# 0113-phobos.net
KiCad netlist of a schematic drawn in EAGLE
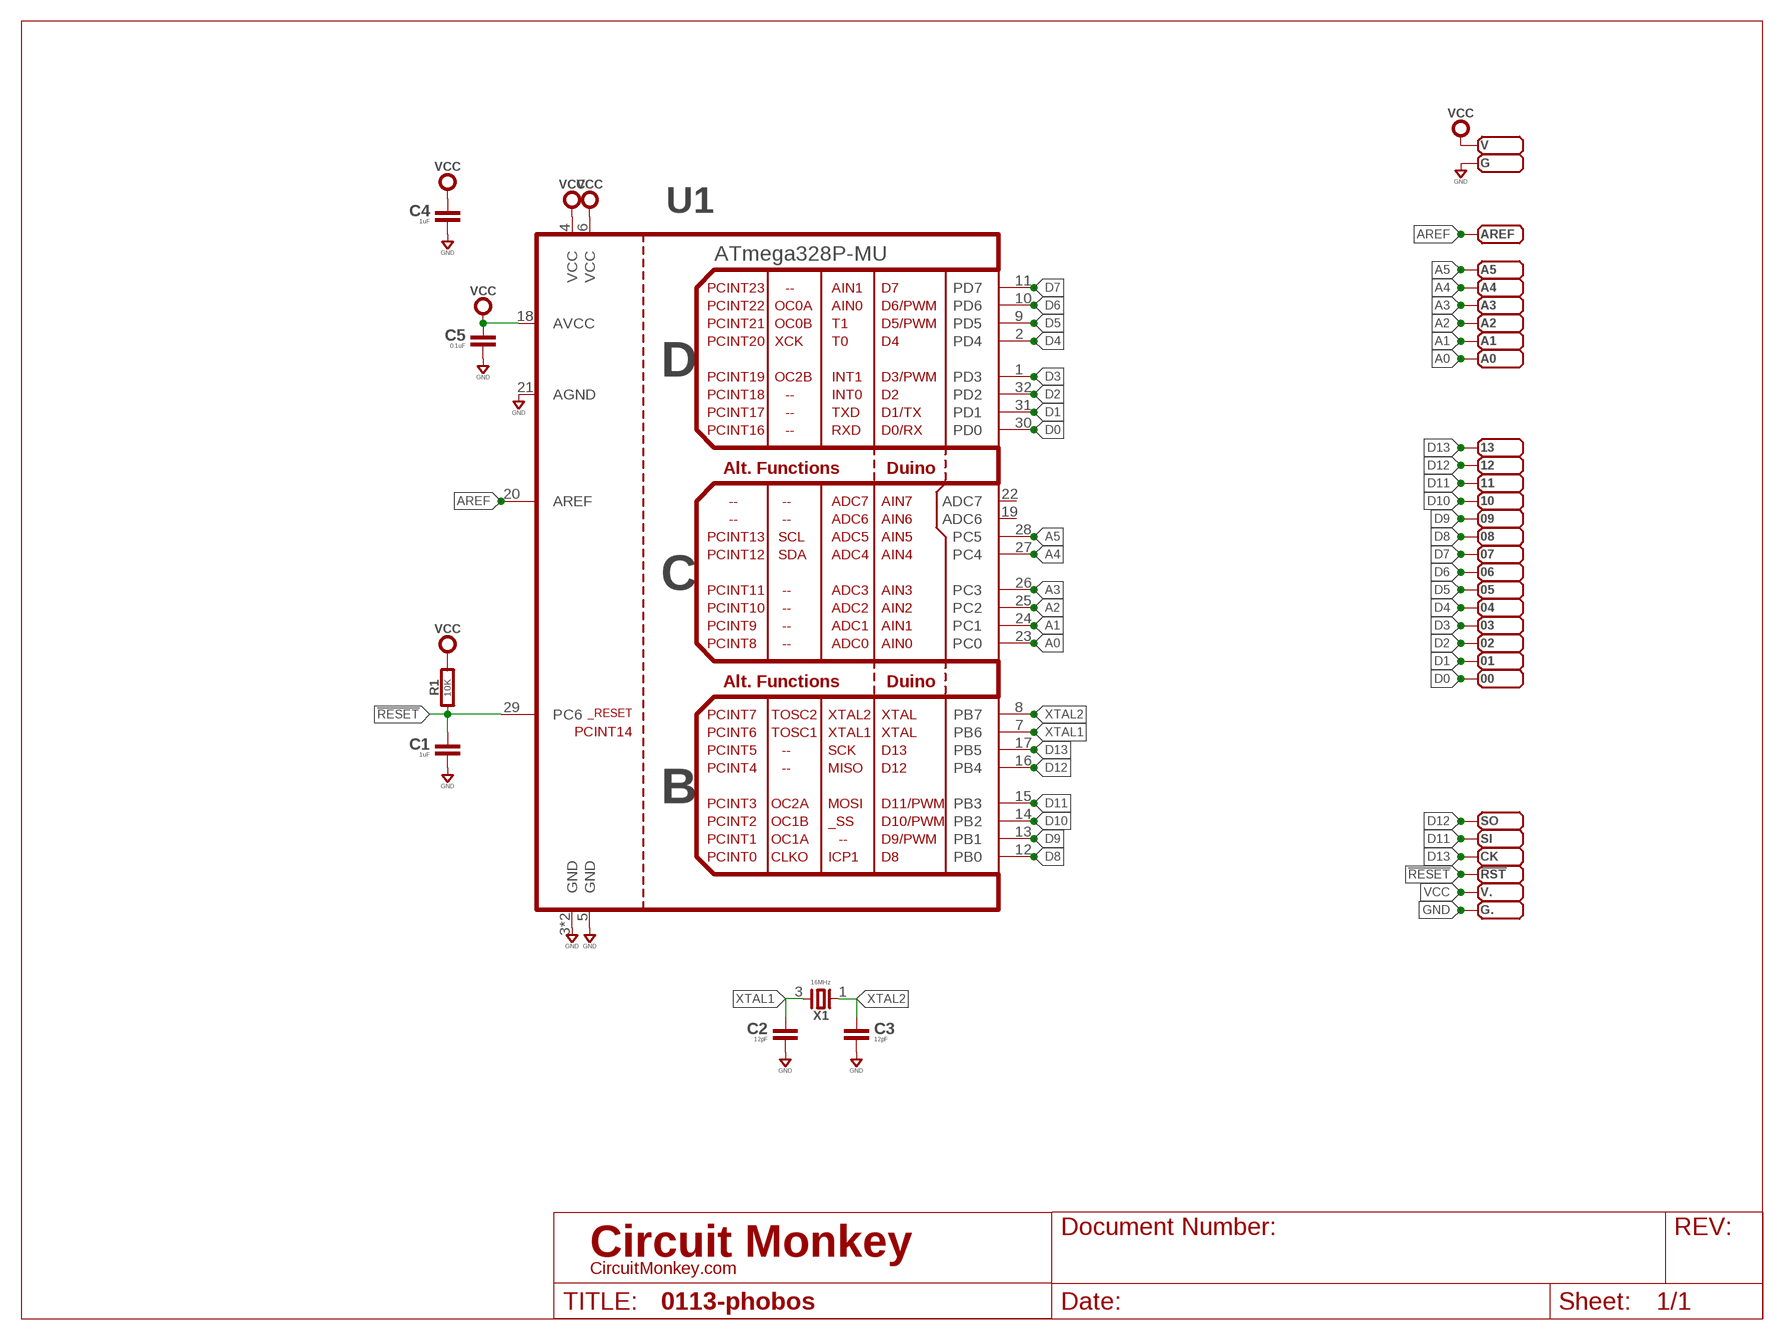
[diagram p0: schematic, sheet 1]

(export (version "E")
  (design (tool "Eeschema 10.0.6"))
  (components
    (comp (ref "!RST")
      (value "PADSMD-070X070")
      (footprint "eagle-import:SMD-070MIL")
      (libsource (lib "eagle-import") (part "PADSMD-070X070"))
    )
    (comp (ref "00")
      (value "PADSMD-070X070")
      (footprint "eagle-import:SMD-070MIL")
      (libsource (lib "eagle-import") (part "PADSMD-070X070"))
    )
    (comp (ref "01")
      (value "PADSMD-070X070")
      (footprint "eagle-import:SMD-070MIL")
      (libsource (lib "eagle-import") (part "PADSMD-070X070"))
    )
    (comp (ref "02")
      (value "PADSMD-070X070")
      (footprint "eagle-import:SMD-070MIL")
      (libsource (lib "eagle-import") (part "PADSMD-070X070"))
    )
    (comp (ref "03")
      (value "PADSMD-070X070")
      (footprint "eagle-import:SMD-070MIL")
      (libsource (lib "eagle-import") (part "PADSMD-070X070"))
    )
    (comp (ref "04")
      (value "PADSMD-070X070")
      (footprint "eagle-import:SMD-070MIL")
      (libsource (lib "eagle-import") (part "PADSMD-070X070"))
    )
    (comp (ref "05")
      (value "PADSMD-070X070")
      (footprint "eagle-import:SMD-070MIL")
      (libsource (lib "eagle-import") (part "PADSMD-070X070"))
    )
    (comp (ref "06")
      (value "PADSMD-070X070")
      (footprint "eagle-import:SMD-070MIL")
      (libsource (lib "eagle-import") (part "PADSMD-070X070"))
    )
    (comp (ref "07")
      (value "PADSMD-070X070")
      (footprint "eagle-import:SMD-070MIL")
      (libsource (lib "eagle-import") (part "PADSMD-070X070"))
    )
    (comp (ref "08")
      (value "PADSMD-070X070")
      (footprint "eagle-import:SMD-070MIL")
      (libsource (lib "eagle-import") (part "PADSMD-070X070"))
    )
    (comp (ref "09")
      (value "PADSMD-070X070")
      (footprint "eagle-import:SMD-070MIL")
      (libsource (lib "eagle-import") (part "PADSMD-070X070"))
    )
    (comp (ref "10")
      (value "PADSMD-070X070")
      (footprint "eagle-import:SMD-070MIL")
      (libsource (lib "eagle-import") (part "PADSMD-070X070"))
    )
    (comp (ref "11")
      (value "PADSMD-070X070")
      (footprint "eagle-import:SMD-070MIL")
      (libsource (lib "eagle-import") (part "PADSMD-070X070"))
    )
    (comp (ref "12")
      (value "PADSMD-070X070")
      (footprint "eagle-import:SMD-070MIL")
      (libsource (lib "eagle-import") (part "PADSMD-070X070"))
    )
    (comp (ref "13")
      (value "PADSMD-070X070")
      (footprint "eagle-import:SMD-070MIL")
      (libsource (lib "eagle-import") (part "PADSMD-070X070"))
    )
    (comp (ref "A0")
      (value "PADSMD-070X070")
      (footprint "eagle-import:SMD-070MIL")
      (libsource (lib "eagle-import") (part "PADSMD-070X070"))
    )
    (comp (ref "A1")
      (value "PADSMD-070X070")
      (footprint "eagle-import:SMD-070MIL")
      (libsource (lib "eagle-import") (part "PADSMD-070X070"))
    )
    (comp (ref "A2")
      (value "PADSMD-070X070")
      (footprint "eagle-import:SMD-070MIL")
      (libsource (lib "eagle-import") (part "PADSMD-070X070"))
    )
    (comp (ref "A3")
      (value "PADSMD-070X070")
      (footprint "eagle-import:SMD-070MIL")
      (libsource (lib "eagle-import") (part "PADSMD-070X070"))
    )
    (comp (ref "A4")
      (value "PADSMD-070X070")
      (footprint "eagle-import:SMD-070MIL")
      (libsource (lib "eagle-import") (part "PADSMD-070X070"))
    )
    (comp (ref "A5")
      (value "PADSMD-070X070")
      (footprint "eagle-import:SMD-070MIL")
      (libsource (lib "eagle-import") (part "PADSMD-070X070"))
    )
    (comp (ref "AREF")
      (value "PADSMD-070X070")
      (footprint "eagle-import:SMD-070MIL")
      (libsource (lib "eagle-import") (part "PADSMD-070X070"))
    )
    (comp (ref "C1")
      (value "1uF")
      (footprint "eagle-import:0402-CAP")
      (libsource (lib "eagle-import") (part "CAPACITOR0402"))
    )
    (comp (ref "C2")
      (value "12pF")
      (footprint "eagle-import:0402-CAP")
      (libsource (lib "eagle-import") (part "CAPACITOR0402"))
    )
    (comp (ref "C3")
      (value "12pF")
      (footprint "eagle-import:0402-CAP")
      (libsource (lib "eagle-import") (part "CAPACITOR0402"))
    )
    (comp (ref "C4")
      (value "1uF")
      (footprint "eagle-import:0402-CAP")
      (libsource (lib "eagle-import") (part "CAPACITOR0402"))
    )
    (comp (ref "C5")
      (value "0.1uF")
      (footprint "eagle-import:0402-CAP")
      (libsource (lib "eagle-import") (part "CAPACITOR0402"))
    )
    (comp (ref "CK")
      (value "PADSMD-070X070")
      (footprint "eagle-import:SMD-070MIL")
      (libsource (lib "eagle-import") (part "PADSMD-070X070"))
    )
    (comp (ref "G")
      (value "PADSMD-070X070")
      (footprint "eagle-import:SMD-070MIL")
      (libsource (lib "eagle-import") (part "PADSMD-070X070"))
    )
    (comp (ref "G.")
      (value "PADSMD-070X070")
      (footprint "eagle-import:SMD-070MIL")
      (libsource (lib "eagle-import") (part "PADSMD-070X070"))
    )
    (comp (ref "R1")
      (value "10K")
      (footprint "eagle-import:0402-RES")
      (libsource (lib "eagle-import") (part "RESISTOR0402"))
    )
    (comp (ref "SI")
      (value "PADSMD-070X070")
      (footprint "eagle-import:SMD-070MIL")
      (libsource (lib "eagle-import") (part "PADSMD-070X070"))
    )
    (comp (ref "SO")
      (value "PADSMD-070X070")
      (footprint "eagle-import:SMD-070MIL")
      (libsource (lib "eagle-import") (part "PADSMD-070X070"))
    )
    (comp (ref "U1")
      (value "ATmega328P-MU")
      (footprint "eagle-import:MLF32")
      (fields (field (name "MF") "Atmel") (field (name "MPN") "atmega328p-mu"))
      (libsource (lib "eagle-import") (part "ATMEGA328MU"))
    )
    (comp (ref "V")
      (value "PADSMD-070X070")
      (footprint "eagle-import:SMD-070MIL")
      (libsource (lib "eagle-import") (part "PADSMD-070X070"))
    )
    (comp (ref "V.")
      (value "PADSMD-070X070")
      (footprint "eagle-import:SMD-070MIL")
      (libsource (lib "eagle-import") (part "PADSMD-070X070"))
    )
    (comp (ref "X1")
      (value "16MHz")
      (footprint "eagle-import:32X25")
      (fields (field (name "MF") "Epson") (field (name "MPN") "FA-238 16.0000MB-K3"))
      (libsource (lib "eagle-import") (part "2P3.2X2.5"))
    )
  )
  (nets
    (net (code "1") (name "/~{RESET}") (class "Default")
      (node (ref "!RST") (pin "1") (pinfunction "PAD_1") (pintype "bidirectional"))
      (node (ref "C1") (pin "1") (pinfunction "1_1") (pintype "passive"))
      (node (ref "R1") (pin "1") (pinfunction "1_1") (pintype "passive"))
      (node (ref "U1") (pin "29") (pinfunction "PC6_29") (pintype "bidirectional"))
    )
    (net (code "2") (name "A0") (class "Default")
      (node (ref "A0") (pin "1") (pinfunction "PAD_1") (pintype "bidirectional"))
      (node (ref "U1") (pin "23") (pinfunction "PC0_23") (pintype "bidirectional"))
    )
    (net (code "3") (name "A1") (class "Default")
      (node (ref "A1") (pin "1") (pinfunction "PAD_1") (pintype "bidirectional"))
      (node (ref "U1") (pin "24") (pinfunction "PC1_24") (pintype "bidirectional"))
    )
    (net (code "4") (name "A2") (class "Default")
      (node (ref "A2") (pin "1") (pinfunction "PAD_1") (pintype "bidirectional"))
      (node (ref "U1") (pin "25") (pinfunction "PC2_25") (pintype "bidirectional"))
    )
    (net (code "5") (name "A3") (class "Default")
      (node (ref "A3") (pin "1") (pinfunction "PAD_1") (pintype "bidirectional"))
      (node (ref "U1") (pin "26") (pinfunction "PC3_26") (pintype "bidirectional"))
    )
    (net (code "6") (name "A4") (class "Default")
      (node (ref "A4") (pin "1") (pinfunction "PAD_1") (pintype "bidirectional"))
      (node (ref "U1") (pin "27") (pinfunction "PC4_27") (pintype "bidirectional"))
    )
    (net (code "7") (name "A5") (class "Default")
      (node (ref "A5") (pin "1") (pinfunction "PAD_1") (pintype "bidirectional"))
      (node (ref "U1") (pin "28") (pinfunction "PC5_28") (pintype "bidirectional"))
    )
    (net (code "8") (name "AREF") (class "Default")
      (node (ref "AREF") (pin "1") (pinfunction "PAD_1") (pintype "bidirectional"))
      (node (ref "U1") (pin "20") (pinfunction "AREF_20") (pintype "input"))
    )
    (net (code "9") (name "D0") (class "Default")
      (node (ref "00") (pin "1") (pinfunction "PAD_1") (pintype "bidirectional"))
      (node (ref "U1") (pin "30") (pinfunction "PD0_30") (pintype "bidirectional"))
    )
    (net (code "10") (name "D1") (class "Default")
      (node (ref "01") (pin "1") (pinfunction "PAD_1") (pintype "bidirectional"))
      (node (ref "U1") (pin "31") (pinfunction "PD1_31") (pintype "bidirectional"))
    )
    (net (code "11") (name "D2") (class "Default")
      (node (ref "02") (pin "1") (pinfunction "PAD_1") (pintype "bidirectional"))
      (node (ref "U1") (pin "32") (pinfunction "PD2_32") (pintype "bidirectional"))
    )
    (net (code "12") (name "D3") (class "Default")
      (node (ref "03") (pin "1") (pinfunction "PAD_1") (pintype "bidirectional"))
      (node (ref "U1") (pin "1") (pinfunction "PD3_1") (pintype "bidirectional"))
    )
    (net (code "13") (name "D4") (class "Default")
      (node (ref "04") (pin "1") (pinfunction "PAD_1") (pintype "bidirectional"))
      (node (ref "U1") (pin "2") (pinfunction "PD4_2") (pintype "bidirectional"))
    )
    (net (code "14") (name "D5") (class "Default")
      (node (ref "05") (pin "1") (pinfunction "PAD_1") (pintype "bidirectional"))
      (node (ref "U1") (pin "9") (pinfunction "PD5_9") (pintype "bidirectional"))
    )
    (net (code "15") (name "D6") (class "Default")
      (node (ref "06") (pin "1") (pinfunction "PAD_1") (pintype "bidirectional"))
      (node (ref "U1") (pin "10") (pinfunction "PD6_10") (pintype "bidirectional"))
    )
    (net (code "16") (name "D7") (class "Default")
      (node (ref "07") (pin "1") (pinfunction "PAD_1") (pintype "bidirectional"))
      (node (ref "U1") (pin "11") (pinfunction "PD7_11") (pintype "bidirectional"))
    )
    (net (code "17") (name "D8") (class "Default")
      (node (ref "08") (pin "1") (pinfunction "PAD_1") (pintype "bidirectional"))
      (node (ref "U1") (pin "12") (pinfunction "PB0_12") (pintype "bidirectional"))
    )
    (net (code "18") (name "D9") (class "Default")
      (node (ref "09") (pin "1") (pinfunction "PAD_1") (pintype "bidirectional"))
      (node (ref "U1") (pin "13") (pinfunction "PB1_13") (pintype "bidirectional"))
    )
    (net (code "19") (name "D10") (class "Default")
      (node (ref "10") (pin "1") (pinfunction "PAD_1") (pintype "bidirectional"))
      (node (ref "U1") (pin "14") (pinfunction "PB2_14") (pintype "bidirectional"))
    )
    (net (code "20") (name "D11") (class "Default")
      (node (ref "11") (pin "1") (pinfunction "PAD_1") (pintype "bidirectional"))
      (node (ref "SI") (pin "1") (pinfunction "PAD_1") (pintype "bidirectional"))
      (node (ref "U1") (pin "15") (pinfunction "PB3_15") (pintype "bidirectional"))
    )
    (net (code "21") (name "D12") (class "Default")
      (node (ref "12") (pin "1") (pinfunction "PAD_1") (pintype "bidirectional"))
      (node (ref "SO") (pin "1") (pinfunction "PAD_1") (pintype "bidirectional"))
      (node (ref "U1") (pin "16") (pinfunction "PB4_16") (pintype "bidirectional"))
    )
    (net (code "22") (name "D13") (class "Default")
      (node (ref "13") (pin "1") (pinfunction "PAD_1") (pintype "bidirectional"))
      (node (ref "CK") (pin "1") (pinfunction "PAD_1") (pintype "bidirectional"))
      (node (ref "U1") (pin "17") (pinfunction "PB5_17") (pintype "bidirectional"))
    )
    (net (code "23") (name "GND") (class "Default")
      (node (ref "C1") (pin "2") (pinfunction "2_2") (pintype "passive"))
      (node (ref "C2") (pin "2") (pinfunction "2_2") (pintype "passive"))
      (node (ref "C3") (pin "2") (pinfunction "2_2") (pintype "passive"))
      (node (ref "C4") (pin "2") (pinfunction "2_2") (pintype "passive"))
      (node (ref "C5") (pin "2") (pinfunction "2_2") (pintype "passive"))
      (node (ref "G") (pin "1") (pinfunction "PAD_1") (pintype "bidirectional"))
      (node (ref "G.") (pin "1") (pinfunction "PAD_1") (pintype "bidirectional"))
      (node (ref "U1") (pin "21") (pinfunction "AGND_21") (pintype "power_in"))
      (node (ref "U1") (pin "3") (pinfunction "GND_3") (pintype "power_in"))
      (node (ref "U1") (pin "5") (pinfunction "GND_5") (pintype "power_in"))
      (node (ref "U1") (pin "PAD") (pinfunction "GND_PAD") (pintype "power_in"))
    )
    (net (code "24") (name "VCC") (class "Default")
      (node (ref "C4") (pin "1") (pinfunction "1_1") (pintype "passive"))
      (node (ref "C5") (pin "1") (pinfunction "1_1") (pintype "passive"))
      (node (ref "R1") (pin "2") (pinfunction "2_2") (pintype "passive"))
      (node (ref "U1") (pin "18") (pinfunction "AVCC_18") (pintype "power_in"))
      (node (ref "U1") (pin "4") (pinfunction "VCC_4") (pintype "power_in"))
      (node (ref "U1") (pin "6") (pinfunction "VCC_6") (pintype "power_in"))
      (node (ref "V") (pin "1") (pinfunction "PAD_1") (pintype "bidirectional"))
      (node (ref "V.") (pin "1") (pinfunction "PAD_1") (pintype "bidirectional"))
    )
    (net (code "25") (name "XTAL1") (class "Default")
      (node (ref "C2") (pin "1") (pinfunction "1_1") (pintype "passive"))
      (node (ref "U1") (pin "7") (pinfunction "PB6_7") (pintype "bidirectional"))
      (node (ref "X1") (pin "3") (pinfunction "P$2_3") (pintype "passive"))
    )
    (net (code "26") (name "XTAL2") (class "Default")
      (node (ref "C3") (pin "1") (pinfunction "1_1") (pintype "passive"))
      (node (ref "U1") (pin "8") (pinfunction "PB7_8") (pintype "bidirectional"))
      (node (ref "X1") (pin "1") (pinfunction "P$1_1") (pintype "passive"))
    )
    (net (code "27") (name "unconnected-(U1-ADC6-Pad19)") (class "Default")
      (node (ref "U1") (pin "19") (pinfunction "ADC6_19") (pintype "bidirectional"))
    )
    (net (code "28") (name "unconnected-(U1-ADC7-Pad22)") (class "Default")
      (node (ref "U1") (pin "22") (pinfunction "ADC7_22") (pintype "bidirectional"))
    )
  )
)
